# EASCapeRev1A.net
KiCad netlist of a schematic drawn in EAGLE
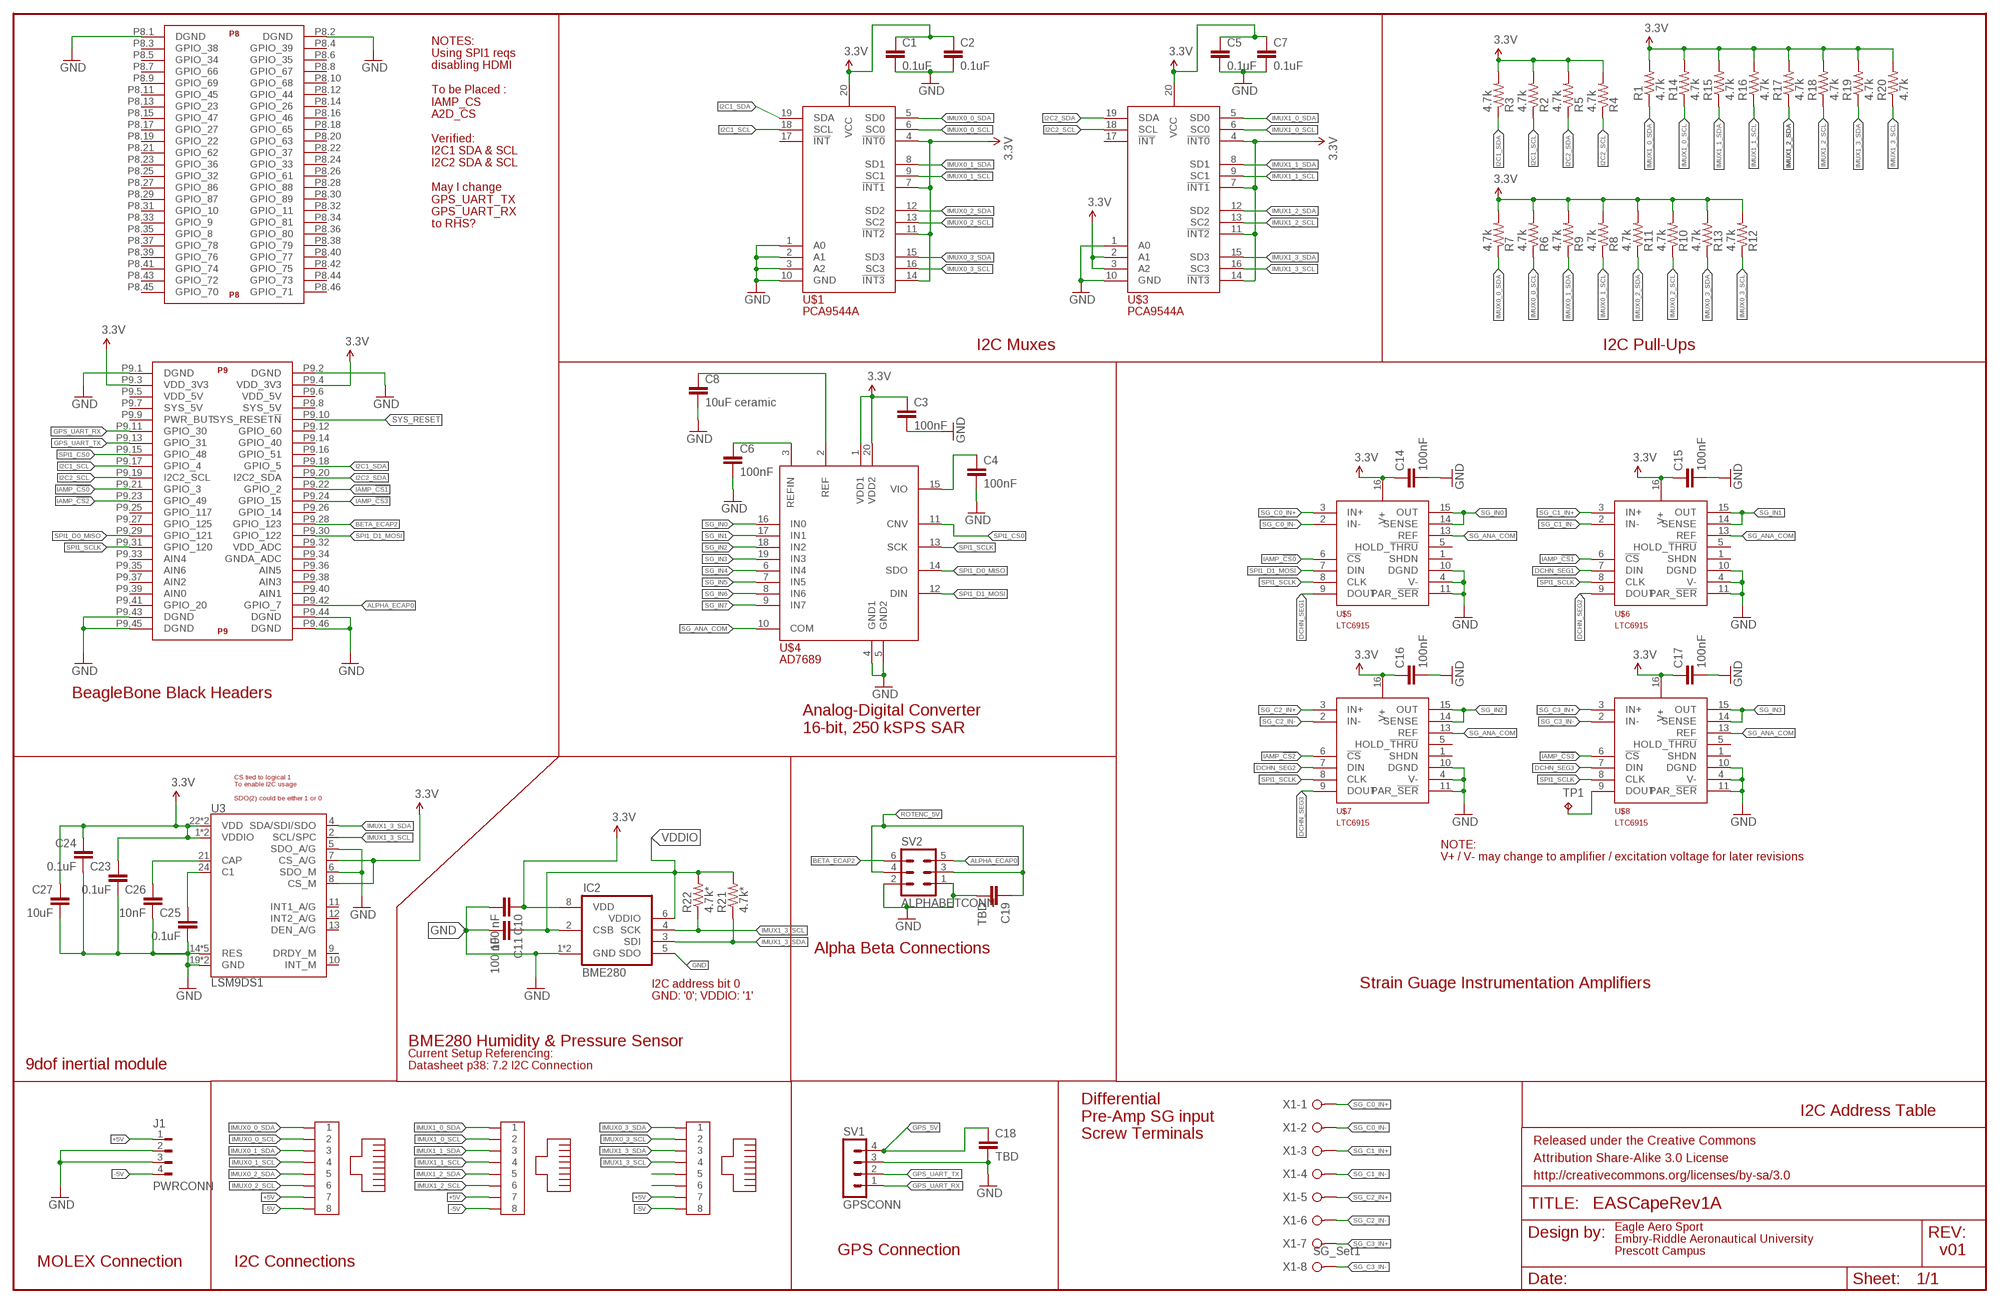
[diagram p0: schematic, sheet 1]

(export (version "E")
  (design (tool "Eeschema 10.0.6"))
  (components
    (comp (ref "C1")
      (value "0.1uF")
      (footprint "eagle-import:0805")
      (libsource (lib "eagle-import") (part "CAP0805"))
    )
    (comp (ref "C2")
      (value "0.1uF")
      (footprint "eagle-import:0805")
      (libsource (lib "eagle-import") (part "CAP0805"))
    )
    (comp (ref "C3")
      (value "100nF")
      (footprint "eagle-import:0805")
      (libsource (lib "eagle-import") (part "CAP0805"))
    )
    (comp (ref "C4")
      (value "100nF")
      (footprint "eagle-import:0805")
      (libsource (lib "eagle-import") (part "CAP0805"))
    )
    (comp (ref "C5")
      (value "0.1uF")
      (footprint "eagle-import:0805")
      (libsource (lib "eagle-import") (part "CAP0805"))
    )
    (comp (ref "C6")
      (value "100nF")
      (footprint "eagle-import:0805")
      (libsource (lib "eagle-import") (part "CAP0805"))
    )
    (comp (ref "C7")
      (value "0.1uF")
      (footprint "eagle-import:0805")
      (libsource (lib "eagle-import") (part "CAP0805"))
    )
    (comp (ref "C8")
      (value "10uF ceramic")
      (footprint "eagle-import:0805")
      (libsource (lib "eagle-import") (part "CAP0805"))
    )
    (comp (ref "C10")
      (value "100 nF")
      (footprint "eagle-import:0805")
      (libsource (lib "eagle-import") (part "CAP0805"))
    )
    (comp (ref "C11")
      (value "100 nF")
      (footprint "eagle-import:0805")
      (libsource (lib "eagle-import") (part "CAP0805"))
    )
    (comp (ref "C14")
      (value "100nF")
      (footprint "eagle-import:0805")
      (libsource (lib "eagle-import") (part "CAP0805"))
    )
    (comp (ref "C15")
      (value "100nF")
      (footprint "eagle-import:0805")
      (libsource (lib "eagle-import") (part "CAP0805"))
    )
    (comp (ref "C16")
      (value "100nF")
      (footprint "eagle-import:0805")
      (libsource (lib "eagle-import") (part "CAP0805"))
    )
    (comp (ref "C17")
      (value "100nF")
      (footprint "eagle-import:0805")
      (libsource (lib "eagle-import") (part "CAP0805"))
    )
    (comp (ref "C18")
      (value "TBD")
      (footprint "eagle-import:0805")
      (libsource (lib "eagle-import") (part "CAP0805"))
    )
    (comp (ref "C19")
      (value "TBD")
      (footprint "eagle-import:0805")
      (libsource (lib "eagle-import") (part "CAP0805"))
    )
    (comp (ref "C23")
      (value "0.1uF")
      (footprint "eagle-import:0805")
      (libsource (lib "eagle-import") (part "CAP0805"))
    )
    (comp (ref "C24")
      (value "0.1uF")
      (footprint "eagle-import:0805")
      (libsource (lib "eagle-import") (part "CAP0805"))
    )
    (comp (ref "C25")
      (value "0.1uF")
      (footprint "eagle-import:0805")
      (libsource (lib "eagle-import") (part "CAP0805"))
    )
    (comp (ref "C26")
      (value "10nF")
      (footprint "eagle-import:0805")
      (libsource (lib "eagle-import") (part "CAP0805"))
    )
    (comp (ref "C27")
      (value "10uF")
      (footprint "eagle-import:0805")
      (libsource (lib "eagle-import") (part "CAP0805"))
    )
    (comp (ref "FRAME1")
      (value "FRAME-LEDGER")
      (footprint "eagle-import:CREATIVE_COMMONS")
      (libsource (lib "eagle-import") (part "FRAME-LEDGER"))
    )
    (comp (ref "IC2")
      (value "BME280")
      (footprint "eagle-import:BME280")
      (libsource (lib "eagle-import") (part "BME280"))
    )
    (comp (ref "J1")
      (value "PWRCONN")
      (footprint "eagle-import:350211")
      (libsource (lib "eagle-import") (part "FLOPPY-4350211"))
    )
    (comp (ref "R1")
      (value "4.7k")
      (footprint "eagle-import:0805")
      (libsource (lib "eagle-import") (part "RESISTOR0805-RES"))
    )
    (comp (ref "R2")
      (value "4.7k")
      (footprint "eagle-import:0805")
      (libsource (lib "eagle-import") (part "RESISTOR0805-RES"))
    )
    (comp (ref "R3")
      (value "4.7k")
      (footprint "eagle-import:0805")
      (libsource (lib "eagle-import") (part "RESISTOR0805-RES"))
    )
    (comp (ref "R4")
      (value "4.7k")
      (footprint "eagle-import:0805")
      (libsource (lib "eagle-import") (part "RESISTOR0805-RES"))
    )
    (comp (ref "R5")
      (value "4.7k")
      (footprint "eagle-import:0805")
      (libsource (lib "eagle-import") (part "RESISTOR0805-RES"))
    )
    (comp (ref "R6")
      (value "4.7k")
      (footprint "eagle-import:0805")
      (libsource (lib "eagle-import") (part "RESISTOR0805-RES"))
    )
    (comp (ref "R7")
      (value "4.7k")
      (footprint "eagle-import:0805")
      (libsource (lib "eagle-import") (part "RESISTOR0805-RES"))
    )
    (comp (ref "R8")
      (value "4.7k")
      (footprint "eagle-import:0805")
      (libsource (lib "eagle-import") (part "RESISTOR0805-RES"))
    )
    (comp (ref "R9")
      (value "4.7k")
      (footprint "eagle-import:0805")
      (libsource (lib "eagle-import") (part "RESISTOR0805-RES"))
    )
    (comp (ref "R10")
      (value "4.7k")
      (footprint "eagle-import:0805")
      (libsource (lib "eagle-import") (part "RESISTOR0805-RES"))
    )
    (comp (ref "R11")
      (value "4.7k")
      (footprint "eagle-import:0805")
      (libsource (lib "eagle-import") (part "RESISTOR0805-RES"))
    )
    (comp (ref "R12")
      (value "4.7k")
      (footprint "eagle-import:0805")
      (libsource (lib "eagle-import") (part "RESISTOR0805-RES"))
    )
    (comp (ref "R13")
      (value "4.7k")
      (footprint "eagle-import:0805")
      (libsource (lib "eagle-import") (part "RESISTOR0805-RES"))
    )
    (comp (ref "R14")
      (value "4.7k")
      (footprint "eagle-import:0805")
      (libsource (lib "eagle-import") (part "RESISTOR0805-RES"))
    )
    (comp (ref "R15")
      (value "4.7k")
      (footprint "eagle-import:0805")
      (libsource (lib "eagle-import") (part "RESISTOR0805-RES"))
    )
    (comp (ref "R16")
      (value "4.7k")
      (footprint "eagle-import:0805")
      (libsource (lib "eagle-import") (part "RESISTOR0805-RES"))
    )
    (comp (ref "R17")
      (value "4.7k")
      (footprint "eagle-import:0805")
      (libsource (lib "eagle-import") (part "RESISTOR0805-RES"))
    )
    (comp (ref "R18")
      (value "4.7k")
      (footprint "eagle-import:0805")
      (libsource (lib "eagle-import") (part "RESISTOR0805-RES"))
    )
    (comp (ref "R19")
      (value "4.7k")
      (footprint "eagle-import:0805")
      (libsource (lib "eagle-import") (part "RESISTOR0805-RES"))
    )
    (comp (ref "R20")
      (value "4.7k")
      (footprint "eagle-import:0805")
      (libsource (lib "eagle-import") (part "RESISTOR0805-RES"))
    )
    (comp (ref "R21")
      (value "4.7k*")
      (footprint "eagle-import:0805")
      (libsource (lib "eagle-import") (part "RESISTOR0805-RES"))
    )
    (comp (ref "R22")
      (value "4.7k*")
      (footprint "eagle-import:0805")
      (libsource (lib "eagle-import") (part "RESISTOR0805-RES"))
    )
    (comp (ref "RJ1")
      (value "MOLEX-RJ45-SMT")
      (footprint "eagle-import:MOLEX-RJ45-SMT")
      (libsource (lib "eagle-import") (part "MOLEX-RJ45-SMT"))
    )
    (comp (ref "RJ2")
      (value "MOLEX-RJ45-SMT")
      (footprint "eagle-import:MOLEX-RJ45-SMT")
      (libsource (lib "eagle-import") (part "MOLEX-RJ45-SMT"))
    )
    (comp (ref "RJ3")
      (value "MOLEX-RJ45-SMT")
      (footprint "eagle-import:MOLEX-RJ45-SMT")
      (libsource (lib "eagle-import") (part "MOLEX-RJ45-SMT"))
    )
    (comp (ref "SV1")
      (value "GPSCONN")
      (footprint "eagle-import:MA04-1")
      (libsource (lib "eagle-import") (part "MA04-1"))
    )
    (comp (ref "SV2")
      (value "ALPHABETCONN")
      (footprint "eagle-import:MA03-2")
      (libsource (lib "eagle-import") (part "MA03-2"))
    )
    (comp (ref "TP1")
      (value "TPTP08R")
      (footprint "eagle-import:TP08R")
      (libsource (lib "eagle-import") (part "TPTP08R"))
    )
    (comp (ref "U$1")
      (value "PCA9544A")
      (footprint "eagle-import:TSSOP20")
      (libsource (lib "eagle-import") (part "PCA9544A"))
    )
    (comp (ref "U$2")
      (value "BEAGLE_BONE_BLACK_CAPE")
      (footprint "eagle-import:BEAGLE_BONE_BLACK_CAPE")
      (libsource (lib "eagle-import") (part "BEAGLE_BONE_BLACK_CAPE"))
    )
    (comp (ref "U$3")
      (value "PCA9544A")
      (footprint "eagle-import:TSSOP20")
      (libsource (lib "eagle-import") (part "PCA9544A"))
    )
    (comp (ref "U$4")
      (value "AD7689")
      (footprint "eagle-import:QFN20")
      (libsource (lib "eagle-import") (part "AD7689"))
    )
    (comp (ref "U$5")
      (value "LTC6915")
      (footprint "eagle-import:SSOP16")
      (libsource (lib "eagle-import") (part "LTC6915"))
    )
    (comp (ref "U$6")
      (value "LTC6915")
      (footprint "eagle-import:SSOP16")
      (libsource (lib "eagle-import") (part "LTC6915"))
    )
    (comp (ref "U$7")
      (value "LTC6915")
      (footprint "eagle-import:SSOP16")
      (libsource (lib "eagle-import") (part "LTC6915"))
    )
    (comp (ref "U$8")
      (value "LTC6915")
      (footprint "eagle-import:SSOP16")
      (libsource (lib "eagle-import") (part "LTC6915"))
    )
    (comp (ref "U3")
      (value "LSM9DS1")
      (footprint "eagle-import:LGA24-8X4")
      (libsource (lib "eagle-import") (part "LSM9DS1"))
    )
    (comp (ref "X1")
      (value "SG_Set1")
      (footprint "eagle-import:W237-8P")
      (libsource (lib "eagle-import") (part "W237-08P"))
    )
  )
  (nets
    (net (code "1") (name "+5V") (class "Default")
      (node (ref "J1") (pin "1") (pinfunction "1_1") (pintype "passive"))
      (node (ref "RJ1") (pin "7") (pinfunction "7_7") (pintype "bidirectional"))
      (node (ref "RJ2") (pin "7") (pinfunction "7_7") (pintype "bidirectional"))
      (node (ref "RJ3") (pin "7") (pinfunction "7_7") (pintype "bidirectional"))
    )
    (net (code "2") (name "-5V") (class "Default")
      (node (ref "J1") (pin "4") (pinfunction "4_4") (pintype "passive"))
      (node (ref "RJ1") (pin "8") (pinfunction "8_8") (pintype "bidirectional"))
      (node (ref "RJ2") (pin "8") (pinfunction "8_8") (pintype "bidirectional"))
      (node (ref "RJ3") (pin "8") (pinfunction "8_8") (pintype "bidirectional"))
    )
    (net (code "3") (name "/IAMP_~{CS0}") (class "Default")
      (node (ref "U$2") (pin "P9.21") (pinfunction "GPIO_3_P9.21") (pintype "bidirectional"))
      (node (ref "U$5") (pin "6") (pinfunction "~{CS}_6") (pintype "bidirectional"))
    )
    (net (code "4") (name "/IAMP_~{CS1}") (class "Default")
      (node (ref "U$2") (pin "P9.22") (pinfunction "GPIO_2_P9.22") (pintype "bidirectional"))
      (node (ref "U$6") (pin "6") (pinfunction "~{CS}_6") (pintype "bidirectional"))
    )
    (net (code "5") (name "/IAMP_~{CS2}") (class "Default")
      (node (ref "U$2") (pin "P9.23") (pinfunction "GPIO_49_P9.23") (pintype "bidirectional"))
      (node (ref "U$7") (pin "6") (pinfunction "~{CS}_6") (pintype "bidirectional"))
    )
    (net (code "6") (name "/IAMP_~{CS3}") (class "Default")
      (node (ref "U$2") (pin "P9.24") (pinfunction "GPIO_15_P9.24") (pintype "bidirectional"))
      (node (ref "U$8") (pin "6") (pinfunction "~{CS}_6") (pintype "bidirectional"))
    )
    (net (code "7") (name "3.3V") (class "Default")
      (node (ref "C1") (pin "1") (pinfunction "1_1") (pintype "passive"))
      (node (ref "C10") (pin "1") (pinfunction "1_1") (pintype "passive"))
      (node (ref "C14") (pin "1") (pinfunction "1_1") (pintype "passive"))
      (node (ref "C15") (pin "1") (pinfunction "1_1") (pintype "passive"))
      (node (ref "C16") (pin "1") (pinfunction "1_1") (pintype "passive"))
      (node (ref "C17") (pin "1") (pinfunction "1_1") (pintype "passive"))
      (node (ref "C2") (pin "1") (pinfunction "1_1") (pintype "passive"))
      (node (ref "C23") (pin "1") (pinfunction "1_1") (pintype "passive"))
      (node (ref "C24") (pin "1") (pinfunction "1_1") (pintype "passive"))
      (node (ref "C27") (pin "1") (pinfunction "1_1") (pintype "passive"))
      (node (ref "C3") (pin "1") (pinfunction "1_1") (pintype "passive"))
      (node (ref "C5") (pin "1") (pinfunction "1_1") (pintype "passive"))
      (node (ref "C7") (pin "1") (pinfunction "1_1") (pintype "passive"))
      (node (ref "IC2") (pin "8") (pinfunction "VDD_8") (pintype "power_in"))
      (node (ref "R1") (pin "2") (pinfunction "2_2") (pintype "passive"))
      (node (ref "R10") (pin "2") (pinfunction "2_2") (pintype "passive"))
      (node (ref "R11") (pin "2") (pinfunction "2_2") (pintype "passive"))
      (node (ref "R12") (pin "2") (pinfunction "2_2") (pintype "passive"))
      (node (ref "R13") (pin "2") (pinfunction "2_2") (pintype "passive"))
      (node (ref "R14") (pin "2") (pinfunction "2_2") (pintype "passive"))
      (node (ref "R15") (pin "2") (pinfunction "2_2") (pintype "passive"))
      (node (ref "R16") (pin "2") (pinfunction "2_2") (pintype "passive"))
      (node (ref "R17") (pin "2") (pinfunction "2_2") (pintype "passive"))
      (node (ref "R18") (pin "2") (pinfunction "2_2") (pintype "passive"))
      (node (ref "R19") (pin "2") (pinfunction "2_2") (pintype "passive"))
      (node (ref "R2") (pin "2") (pinfunction "2_2") (pintype "passive"))
      (node (ref "R20") (pin "2") (pinfunction "2_2") (pintype "passive"))
      (node (ref "R3") (pin "2") (pinfunction "2_2") (pintype "passive"))
      (node (ref "R4") (pin "2") (pinfunction "2_2") (pintype "passive"))
      (node (ref "R5") (pin "2") (pinfunction "2_2") (pintype "passive"))
      (node (ref "R6") (pin "2") (pinfunction "2_2") (pintype "passive"))
      (node (ref "R7") (pin "2") (pinfunction "2_2") (pintype "passive"))
      (node (ref "R8") (pin "2") (pinfunction "2_2") (pintype "passive"))
      (node (ref "R9") (pin "2") (pinfunction "2_2") (pintype "passive"))
      (node (ref "U$1") (pin "11") (pinfunction "~{INT2}_11") (pintype "input"))
      (node (ref "U$1") (pin "14") (pinfunction "~{INT3}_14") (pintype "input"))
      (node (ref "U$1") (pin "20") (pinfunction "VCC_20") (pintype "power_in"))
      (node (ref "U$1") (pin "4") (pinfunction "~{INT0}_4") (pintype "input"))
      (node (ref "U$1") (pin "7") (pinfunction "~{INT1}_7") (pintype "input"))
      (node (ref "U$2") (pin "P9.3") (pinfunction "VDD_3V3_P9.3") (pintype "bidirectional"))
      (node (ref "U$2") (pin "P9.4") (pinfunction "VDD_3V3_P9.4") (pintype "bidirectional"))
      (node (ref "U$3") (pin "11") (pinfunction "~{INT2}_11") (pintype "input"))
      (node (ref "U$3") (pin "14") (pinfunction "~{INT3}_14") (pintype "input"))
      (node (ref "U$3") (pin "2") (pinfunction "A1_2") (pintype "input"))
      (node (ref "U$3") (pin "20") (pinfunction "VCC_20") (pintype "power_in"))
      (node (ref "U$3") (pin "3") (pinfunction "A2_3") (pintype "input"))
      (node (ref "U$3") (pin "4") (pinfunction "~{INT0}_4") (pintype "input"))
      (node (ref "U$3") (pin "7") (pinfunction "~{INT1}_7") (pintype "input"))
      (node (ref "U$4") (pin "1") (pinfunction "VDD1_1") (pintype "bidirectional"))
      (node (ref "U$4") (pin "20") (pinfunction "VDD2_20") (pintype "bidirectional"))
      (node (ref "U$5") (pin "16") (pinfunction "V+_16") (pintype "bidirectional"))
      (node (ref "U$6") (pin "16") (pinfunction "V+_16") (pintype "bidirectional"))
      (node (ref "U$7") (pin "16") (pinfunction "V+_16") (pintype "bidirectional"))
      (node (ref "U$8") (pin "16") (pinfunction "V+_16") (pintype "bidirectional"))
      (node (ref "U3") (pin "1") (pinfunction "VDDIO_1") (pintype "bidirectional"))
      (node (ref "U3") (pin "22") (pinfunction "VDD_22") (pintype "bidirectional"))
      (node (ref "U3") (pin "23") (pinfunction "VDD_23") (pintype "bidirectional"))
      (node (ref "U3") (pin "3") (pinfunction "VDDIO_3") (pintype "bidirectional"))
      (node (ref "U3") (pin "7") (pinfunction "CS_A/G_7") (pintype "bidirectional"))
      (node (ref "U3") (pin "8") (pinfunction "CS_M_8") (pintype "bidirectional"))
    )
    (net (code "8") (name "ALPHA_ECAP0") (class "Default")
      (node (ref "SV2") (pin "5") (pinfunction "5_5") (pintype "passive"))
      (node (ref "U$2") (pin "P9.42") (pinfunction "GPIO_7_P9.42") (pintype "bidirectional"))
    )
    (net (code "9") (name "BETA_ECAP2") (class "Default")
      (node (ref "SV2") (pin "6") (pinfunction "6_6") (pintype "passive"))
      (node (ref "U$2") (pin "P9.28") (pinfunction "GPIO_123_P9.28") (pintype "bidirectional"))
    )
    (net (code "10") (name "DCHN_SEG1") (class "Default")
      (node (ref "U$5") (pin "9") (pinfunction "DOUT_9") (pintype "bidirectional"))
      (node (ref "U$6") (pin "7") (pinfunction "DIN_7") (pintype "bidirectional"))
    )
    (net (code "11") (name "DCHN_SEG2") (class "Default")
      (node (ref "U$6") (pin "9") (pinfunction "DOUT_9") (pintype "bidirectional"))
      (node (ref "U$7") (pin "7") (pinfunction "DIN_7") (pintype "bidirectional"))
    )
    (net (code "12") (name "DCHN_SEG3") (class "Default")
      (node (ref "U$7") (pin "9") (pinfunction "DOUT_9") (pintype "bidirectional"))
      (node (ref "U$8") (pin "7") (pinfunction "DIN_7") (pintype "bidirectional"))
    )
    (net (code "13") (name "GND") (class "Default")
      (node (ref "C1") (pin "2") (pinfunction "2_2") (pintype "passive"))
      (node (ref "C10") (pin "2") (pinfunction "2_2") (pintype "passive"))
      (node (ref "C11") (pin "2") (pinfunction "2_2") (pintype "passive"))
      (node (ref "C14") (pin "2") (pinfunction "2_2") (pintype "passive"))
      (node (ref "C15") (pin "2") (pinfunction "2_2") (pintype "passive"))
      (node (ref "C16") (pin "2") (pinfunction "2_2") (pintype "passive"))
      (node (ref "C17") (pin "2") (pinfunction "2_2") (pintype "passive"))
      (node (ref "C18") (pin "2") (pinfunction "2_2") (pintype "passive"))
      (node (ref "C19") (pin "2") (pinfunction "2_2") (pintype "passive"))
      (node (ref "C2") (pin "2") (pinfunction "2_2") (pintype "passive"))
      (node (ref "C23") (pin "2") (pinfunction "2_2") (pintype "passive"))
      (node (ref "C24") (pin "2") (pinfunction "2_2") (pintype "passive"))
      (node (ref "C25") (pin "2") (pinfunction "2_2") (pintype "passive"))
      (node (ref "C26") (pin "2") (pinfunction "2_2") (pintype "passive"))
      (node (ref "C27") (pin "2") (pinfunction "2_2") (pintype "passive"))
      (node (ref "C3") (pin "2") (pinfunction "2_2") (pintype "passive"))
      (node (ref "C4") (pin "2") (pinfunction "2_2") (pintype "passive"))
      (node (ref "C5") (pin "2") (pinfunction "2_2") (pintype "passive"))
      (node (ref "C6") (pin "2") (pinfunction "2_2") (pintype "passive"))
      (node (ref "C7") (pin "2") (pinfunction "2_2") (pintype "passive"))
      (node (ref "C8") (pin "2") (pinfunction "2_2") (pintype "passive"))
      (node (ref "IC2") (pin "1") (pinfunction "GND_1") (pintype "power_in"))
      (node (ref "IC2") (pin "5") (pinfunction "SDO_5") (pintype "input"))
      (node (ref "IC2") (pin "7") (pinfunction "GND_7") (pintype "power_in"))
      (node (ref "J1") (pin "2") (pinfunction "2_2") (pintype "passive"))
      (node (ref "J1") (pin "3") (pinfunction "3_3") (pintype "passive"))
      (node (ref "SV1") (pin "3") (pinfunction "3_3") (pintype "passive"))
      (node (ref "SV2") (pin "1") (pinfunction "1_1") (pintype "passive"))
      (node (ref "SV2") (pin "2") (pinfunction "2_2") (pintype "passive"))
      (node (ref "U$1") (pin "1") (pinfunction "A0_1") (pintype "input"))
      (node (ref "U$1") (pin "10") (pinfunction "GND_10") (pintype "power_in"))
      (node (ref "U$1") (pin "2") (pinfunction "A1_2") (pintype "input"))
      (node (ref "U$1") (pin "3") (pinfunction "A2_3") (pintype "input"))
      (node (ref "U$2") (pin "P8.1") (pinfunction "DGND_P8.1") (pintype "bidirectional"))
      (node (ref "U$2") (pin "P8.2") (pinfunction "DGND_P8.2") (pintype "bidirectional"))
      (node (ref "U$2") (pin "P9.1") (pinfunction "DGND_P9.1") (pintype "bidirectional"))
      (node (ref "U$2") (pin "P9.2") (pinfunction "DGND_P9.2") (pintype "bidirectional"))
      (node (ref "U$2") (pin "P9.43") (pinfunction "DGND_P9.43") (pintype "bidirectional"))
      (node (ref "U$2") (pin "P9.44") (pinfunction "DGND_P9.44") (pintype "bidirectional"))
      (node (ref "U$2") (pin "P9.45") (pinfunction "DGND_P9.45") (pintype "bidirectional"))
      (node (ref "U$2") (pin "P9.46") (pinfunction "DGND_P9.46") (pintype "bidirectional"))
      (node (ref "U$3") (pin "1") (pinfunction "A0_1") (pintype "input"))
      (node (ref "U$3") (pin "10") (pinfunction "GND_10") (pintype "power_in"))
      (node (ref "U$4") (pin "4") (pinfunction "GND1_4") (pintype "bidirectional"))
      (node (ref "U$4") (pin "5") (pinfunction "GND2_5") (pintype "bidirectional"))
      (node (ref "U$5") (pin "10") (pinfunction "DGND_10") (pintype "bidirectional"))
      (node (ref "U$5") (pin "11") (pinfunction "PAR_~{SER}_11") (pintype "bidirectional"))
      (node (ref "U$5") (pin "4") (pinfunction "V-_4") (pintype "bidirectional"))
      (node (ref "U$6") (pin "10") (pinfunction "DGND_10") (pintype "bidirectional"))
      (node (ref "U$6") (pin "11") (pinfunction "PAR_~{SER}_11") (pintype "bidirectional"))
      (node (ref "U$6") (pin "4") (pinfunction "V-_4") (pintype "bidirectional"))
      (node (ref "U$7") (pin "10") (pinfunction "DGND_10") (pintype "bidirectional"))
      (node (ref "U$7") (pin "11") (pinfunction "PAR_~{SER}_11") (pintype "bidirectional"))
      (node (ref "U$7") (pin "4") (pinfunction "V-_4") (pintype "bidirectional"))
      (node (ref "U$8") (pin "10") (pinfunction "DGND_10") (pintype "bidirectional"))
      (node (ref "U$8") (pin "11") (pinfunction "PAR_~{SER}_11") (pintype "bidirectional"))
      (node (ref "U$8") (pin "4") (pinfunction "V-_4") (pintype "bidirectional"))
      (node (ref "U3") (pin "14") (pinfunction "RES_14") (pintype "bidirectional"))
      (node (ref "U3") (pin "15") (pinfunction "RES_15") (pintype "bidirectional"))
      (node (ref "U3") (pin "16") (pinfunction "RES_16") (pintype "bidirectional"))
      (node (ref "U3") (pin "17") (pinfunction "RES_17") (pintype "bidirectional"))
      (node (ref "U3") (pin "18") (pinfunction "RES_18") (pintype "bidirectional"))
      (node (ref "U3") (pin "19") (pinfunction "GND_19") (pintype "bidirectional"))
      (node (ref "U3") (pin "20") (pinfunction "GND_20") (pintype "bidirectional"))
      (node (ref "U3") (pin "5") (pinfunction "SDO_A/G_5") (pintype "bidirectional"))
      (node (ref "U3") (pin "6") (pinfunction "SDO_M_6") (pintype "bidirectional"))
    )
    (net (code "14") (name "GPS_5V") (class "Default")
      (node (ref "C18") (pin "1") (pinfunction "1_1") (pintype "passive"))
      (node (ref "SV1") (pin "4") (pinfunction "4_4") (pintype "passive"))
    )
    (net (code "15") (name "GPS_UART_RX") (class "Default")
      (node (ref "SV1") (pin "1") (pinfunction "1_1") (pintype "passive"))
      (node (ref "U$2") (pin "P9.11") (pinfunction "GPIO_30_P9.11") (pintype "bidirectional"))
    )
    (net (code "16") (name "GPS_UART_TX") (class "Default")
      (node (ref "SV1") (pin "2") (pinfunction "2_2") (pintype "passive"))
      (node (ref "U$2") (pin "P9.13") (pinfunction "GPIO_31_P9.13") (pintype "bidirectional"))
    )
    (net (code "17") (name "I2C1_SCL") (class "Default")
      (node (ref "R2") (pin "1") (pinfunction "1_1") (pintype "passive"))
      (node (ref "U$1") (pin "18") (pinfunction "SCL_18") (pintype "input"))
      (node (ref "U$2") (pin "P9.17") (pinfunction "GPIO_4_P9.17") (pintype "bidirectional"))
    )
    (net (code "18") (name "I2C1_SDA") (class "Default")
      (node (ref "R3") (pin "1") (pinfunction "1_1") (pintype "passive"))
      (node (ref "U$1") (pin "19") (pinfunction "SDA_19") (pintype "bidirectional"))
      (node (ref "U$2") (pin "P9.18") (pinfunction "GPIO_5_P9.18") (pintype "bidirectional"))
    )
    (net (code "19") (name "I2C2_SCL") (class "Default")
      (node (ref "R4") (pin "1") (pinfunction "1_1") (pintype "passive"))
      (node (ref "U$2") (pin "P9.19") (pinfunction "I2C2_SCL_P9.19") (pintype "bidirectional"))
      (node (ref "U$3") (pin "18") (pinfunction "SCL_18") (pintype "input"))
    )
    (net (code "20") (name "I2C2_SDA") (class "Default")
      (node (ref "R5") (pin "1") (pinfunction "1_1") (pintype "passive"))
      (node (ref "U$2") (pin "P9.20") (pinfunction "I2C2_SDA_P9.20") (pintype "bidirectional"))
      (node (ref "U$3") (pin "19") (pinfunction "SDA_19") (pintype "bidirectional"))
    )
    (net (code "21") (name "IMUX0_0_SCL") (class "Default")
      (node (ref "R6") (pin "1") (pinfunction "1_1") (pintype "passive"))
      (node (ref "RJ1") (pin "2") (pinfunction "2_2") (pintype "bidirectional"))
      (node (ref "U$1") (pin "6") (pinfunction "SC0_6") (pintype "output"))
    )
    (net (code "22") (name "IMUX0_0_SDA") (class "Default")
      (node (ref "R7") (pin "1") (pinfunction "1_1") (pintype "passive"))
      (node (ref "RJ1") (pin "1") (pinfunction "1_1") (pintype "bidirectional"))
      (node (ref "U$1") (pin "5") (pinfunction "SD0_5") (pintype "bidirectional"))
    )
    (net (code "23") (name "IMUX0_1_SCL") (class "Default")
      (node (ref "R8") (pin "1") (pinfunction "1_1") (pintype "passive"))
      (node (ref "RJ1") (pin "4") (pinfunction "4_4") (pintype "bidirectional"))
      (node (ref "U$1") (pin "9") (pinfunction "SC1_9") (pintype "output"))
    )
    (net (code "24") (name "IMUX0_1_SDA") (class "Default")
      (node (ref "R9") (pin "1") (pinfunction "1_1") (pintype "passive"))
      (node (ref "RJ1") (pin "3") (pinfunction "3_3") (pintype "bidirectional"))
      (node (ref "U$1") (pin "8") (pinfunction "SD1_8") (pintype "bidirectional"))
    )
    (net (code "25") (name "IMUX0_2_SCL") (class "Default")
      (node (ref "R10") (pin "1") (pinfunction "1_1") (pintype "passive"))
      (node (ref "RJ1") (pin "6") (pinfunction "6_6") (pintype "bidirectional"))
      (node (ref "U$1") (pin "13") (pinfunction "SC2_13") (pintype "output"))
    )
    (net (code "26") (name "IMUX0_2_SDA") (class "Default")
      (node (ref "R11") (pin "1") (pinfunction "1_1") (pintype "passive"))
      (node (ref "RJ1") (pin "5") (pinfunction "5_5") (pintype "bidirectional"))
      (node (ref "U$1") (pin "12") (pinfunction "SD2_12") (pintype "bidirectional"))
    )
    (net (code "27") (name "IMUX0_3_SCL") (class "Default")
      (node (ref "R12") (pin "1") (pinfunction "1_1") (pintype "passive"))
      (node (ref "RJ3") (pin "2") (pinfunction "2_2") (pintype "bidirectional"))
      (node (ref "U$1") (pin "16") (pinfunction "SC3_16") (pintype "output"))
    )
    (net (code "28") (name "IMUX0_3_SDA") (class "Default")
      (node (ref "R13") (pin "1") (pinfunction "1_1") (pintype "passive"))
      (node (ref "RJ3") (pin "1") (pinfunction "1_1") (pintype "bidirectional"))
      (node (ref "U$1") (pin "15") (pinfunction "SD3_15") (pintype "bidirectional"))
    )
    (net (code "29") (name "IMUX1_0_SCL") (class "Default")
      (node (ref "R14") (pin "1") (pinfunction "1_1") (pintype "passive"))
      (node (ref "RJ2") (pin "2") (pinfunction "2_2") (pintype "bidirectional"))
      (node (ref "U$3") (pin "6") (pinfunction "SC0_6") (pintype "output"))
    )
    (net (code "30") (name "IMUX1_0_SDA") (class "Default")
      (node (ref "R1") (pin "1") (pinfunction "1_1") (pintype "passive"))
      (node (ref "RJ2") (pin "1") (pinfunction "1_1") (pintype "bidirectional"))
      (node (ref "U$3") (pin "5") (pinfunction "SD0_5") (pintype "bidirectional"))
    )
    (net (code "31") (name "IMUX1_1_SCL") (class "Default")
      (node (ref "R16") (pin "1") (pinfunction "1_1") (pintype "passive"))
      (node (ref "RJ2") (pin "4") (pinfunction "4_4") (pintype "bidirectional"))
      (node (ref "U$3") (pin "9") (pinfunction "SC1_9") (pintype "output"))
    )
    (net (code "32") (name "IMUX1_1_SDA") (class "Default")
      (node (ref "R15") (pin "1") (pinfunction "1_1") (pintype "passive"))
      (node (ref "RJ2") (pin "3") (pinfunction "3_3") (pintype "bidirectional"))
      (node (ref "U$3") (pin "8") (pinfunction "SD1_8") (pintype "bidirectional"))
    )
    (net (code "33") (name "IMUX1_2_SCL") (class "Default")
      (node (ref "R18") (pin "1") (pinfunction "1_1") (pintype "passive"))
      (node (ref "RJ2") (pin "6") (pinfunction "6_6") (pintype "bidirectional"))
      (node (ref "U$3") (pin "13") (pinfunction "SC2_13") (pintype "output"))
    )
    (net (code "34") (name "IMUX1_2_SDA") (class "Default")
      (node (ref "R17") (pin "1") (pinfunction "1_1") (pintype "passive"))
      (node (ref "RJ2") (pin "5") (pinfunction "5_5") (pintype "bidirectional"))
      (node (ref "U$3") (pin "12") (pinfunction "SD2_12") (pintype "bidirectional"))
    )
    (net (code "35") (name "IMUX1_3_SCL") (class "Default")
      (node (ref "IC2") (pin "4") (pinfunction "SCK_4") (pintype "bidirectional"))
      (node (ref "R20") (pin "1") (pinfunction "1_1") (pintype "passive"))
      (node (ref "R22") (pin "1") (pinfunction "1_1") (pintype "passive"))
      (node (ref "RJ3") (pin "4") (pinfunction "4_4") (pintype "bidirectional"))
      (node (ref "U$3") (pin "16") (pinfunction "SC3_16") (pintype "output"))
      (node (ref "U3") (pin "2") (pinfunction "SCL/SPC_2") (pintype "bidirectional"))
    )
    (net (code "36") (name "IMUX1_3_SDA") (class "Default")
      (node (ref "IC2") (pin "3") (pinfunction "SDI_3") (pintype "bidirectional"))
      (node (ref "R19") (pin "1") (pinfunction "1_1") (pintype "passive"))
      (node (ref "R21") (pin "1") (pinfunction "1_1") (pintype "passive"))
      (node (ref "RJ3") (pin "3") (pinfunction "3_3") (pintype "bidirectional"))
      (node (ref "U$3") (pin "15") (pinfunction "SD3_15") (pintype "bidirectional"))
      (node (ref "U3") (pin "4") (pinfunction "SDA/SDI/SDO_4") (pintype "bidirectional"))
    )
    (net (code "37") (name "Net-(U$4-REF)") (class "Default")
      (node (ref "C8") (pin "1") (pinfunction "1_1") (pintype "passive"))
      (node (ref "U$4") (pin "2") (pinfunction "REF_2") (pintype "bidirectional"))
    )
    (net (code "38") (name "Net-(U$4-REFIN)") (class "Default")
      (node (ref "C6") (pin "1") (pinfunction "1_1") (pintype "passive"))
      (node (ref "U$4") (pin "3") (pinfunction "REFIN_3") (pintype "bidirectional"))
    )
    (net (code "39") (name "Net-(U$4-VIO)") (class "Default")
      (node (ref "C4") (pin "1") (pinfunction "1_1") (pintype "passive"))
      (node (ref "U$4") (pin "15") (pinfunction "VIO_15") (pintype "bidirectional"))
    )
    (net (code "40") (name "Net-(U$8-DOUT)") (class "Default")
      (node (ref "TP1") (pin "TP") (pinfunction "TP_TP") (pintype "input"))
      (node (ref "U$8") (pin "9") (pinfunction "DOUT_9") (pintype "bidirectional"))
    )
    (net (code "41") (name "Net-(U3-C1)") (class "Default")
      (node (ref "C25") (pin "1") (pinfunction "1_1") (pintype "passive"))
      (node (ref "U3") (pin "24") (pinfunction "C1_24") (pintype "bidirectional"))
    )
    (net (code "42") (name "Net-(U3-CAP)") (class "Default")
      (node (ref "C26") (pin "1") (pinfunction "1_1") (pintype "passive"))
      (node (ref "U3") (pin "21") (pinfunction "CAP_21") (pintype "bidirectional"))
    )
    (net (code "43") (name "ROTENC_5V") (class "Default")
      (node (ref "C19") (pin "1") (pinfunction "1_1") (pintype "passive"))
      (node (ref "SV2") (pin "3") (pinfunction "3_3") (pintype "passive"))
      (node (ref "SV2") (pin "4") (pinfunction "4_4") (pintype "passive"))
    )
    (net (code "44") (name "SG_ANA_COM") (class "Default")
      (node (ref "U$4") (pin "10") (pinfunction "COM_10") (pintype "bidirectional"))
      (node (ref "U$5") (pin "13") (pinfunction "REF_13") (pintype "bidirectional"))
      (node (ref "U$6") (pin "13") (pinfunction "REF_13") (pintype "bidirectional"))
      (node (ref "U$7") (pin "13") (pinfunction "REF_13") (pintype "bidirectional"))
      (node (ref "U$8") (pin "13") (pinfunction "REF_13") (pintype "bidirectional"))
    )
    (net (code "45") (name "SG_C0_IN+") (class "Default")
      (node (ref "U$5") (pin "3") (pinfunction "IN+_3") (pintype "bidirectional"))
      (node (ref "X1") (pin "1") (pinfunction "KL_1") (pintype "passive"))
    )
    (net (code "46") (name "SG_C0_IN-") (class "Default")
      (node (ref "U$5") (pin "2") (pinfunction "IN-_2") (pintype "bidirectional"))
      (node (ref "X1") (pin "2") (pinfunction "KL_2") (pintype "passive"))
    )
    (net (code "47") (name "SG_C1_IN+") (class "Default")
      (node (ref "U$6") (pin "3") (pinfunction "IN+_3") (pintype "bidirectional"))
      (node (ref "X1") (pin "3") (pinfunction "KL_3") (pintype "passive"))
    )
    (net (code "48") (name "SG_C1_IN-") (class "Default")
      (node (ref "U$6") (pin "2") (pinfunction "IN-_2") (pintype "bidirectional"))
      (node (ref "X1") (pin "4") (pinfunction "KL_4") (pintype "passive"))
    )
    (net (code "49") (name "SG_C2_IN+") (class "Default")
      (node (ref "U$7") (pin "3") (pinfunction "IN+_3") (pintype "bidirectional"))
      (node (ref "X1") (pin "5") (pinfunction "KL_5") (pintype "passive"))
    )
    (net (code "50") (name "SG_C2_IN-") (class "Default")
      (node (ref "U$7") (pin "2") (pinfunction "IN-_2") (pintype "bidirectional"))
      (node (ref "X1") (pin "6") (pinfunction "KL_6") (pintype "passive"))
    )
    (net (code "51") (name "SG_C3_IN+") (class "Default")
      (node (ref "U$8") (pin "3") (pinfunction "IN+_3") (pintype "bidirectional"))
      (node (ref "X1") (pin "7") (pinfunction "KL_7") (pintype "passive"))
    )
    (net (code "52") (name "SG_C3_IN-") (class "Default")
      (node (ref "U$8") (pin "2") (pinfunction "IN-_2") (pintype "bidirectional"))
      (node (ref "X1") (pin "8") (pinfunction "KL_8") (pintype "passive"))
    )
    (net (code "53") (name "SG_IN0") (class "Default")
      (node (ref "U$4") (pin "16") (pinfunction "IN0_16") (pintype "bidirectional"))
      (node (ref "U$5") (pin "14") (pinfunction "SENSE_14") (pintype "bidirectional"))
      (node (ref "U$5") (pin "15") (pinfunction "OUT_15") (pintype "bidirectional"))
    )
    (net (code "54") (name "SG_IN1") (class "Default")
      (node (ref "U$4") (pin "17") (pinfunction "IN1_17") (pintype "bidirectional"))
      (node (ref "U$6") (pin "14") (pinfunction "SENSE_14") (pintype "bidirectional"))
      (node (ref "U$6") (pin "15") (pinfunction "OUT_15") (pintype "bidirectional"))
    )
    (net (code "55") (name "SG_IN2") (class "Default")
      (node (ref "U$4") (pin "18") (pinfunction "IN2_18") (pintype "bidirectional"))
      (node (ref "U$7") (pin "14") (pinfunction "SENSE_14") (pintype "bidirectional"))
      (node (ref "U$7") (pin "15") (pinfunction "OUT_15") (pintype "bidirectional"))
    )
    (net (code "56") (name "SG_IN3") (class "Default")
      (node (ref "U$4") (pin "19") (pinfunction "IN3_19") (pintype "bidirectional"))
      (node (ref "U$8") (pin "14") (pinfunction "SENSE_14") (pintype "bidirectional"))
      (node (ref "U$8") (pin "15") (pinfunction "OUT_15") (pintype "bidirectional"))
    )
    (net (code "57") (name "SG_IN4") (class "Default")
      (node (ref "U$4") (pin "6") (pinfunction "IN4_6") (pintype "bidirectional"))
    )
    (net (code "58") (name "SG_IN5") (class "Default")
      (node (ref "U$4") (pin "7") (pinfunction "IN5_7") (pintype "bidirectional"))
    )
    (net (code "59") (name "SG_IN6") (class "Default")
      (node (ref "U$4") (pin "8") (pinfunction "IN6_8") (pintype "bidirectional"))
    )
    (net (code "60") (name "SG_IN7") (class "Default")
      (node (ref "U$4") (pin "9") (pinfunction "IN7_9") (pintype "bidirectional"))
    )
    (net (code "61") (name "SPI1_CS0") (class "Default")
      (node (ref "U$2") (pin "P9.15") (pinfunction "GPIO_48_P9.15") (pintype "bidirectional"))
      (node (ref "U$4") (pin "11") (pinfunction "CNV_11") (pintype "bidirectional"))
    )
    (net (code "62") (name "SPI1_D0_MISO") (class "Default")
      (node (ref "U$2") (pin "P9.29") (pinfunction "GPIO_121_P9.29") (pintype "bidirectional"))
      (node (ref "U$4") (pin "14") (pinfunction "SDO_14") (pintype "bidirectional"))
    )
    (net (code "63") (name "SPI1_D1_MOSI") (class "Default")
      (node (ref "U$2") (pin "P9.30") (pinfunction "GPIO_122_P9.30") (pintype "bidirectional"))
      (node (ref "U$4") (pin "12") (pinfunction "DIN_12") (pintype "bidirectional"))
      (node (ref "U$5") (pin "7") (pinfunction "DIN_7") (pintype "bidirectional"))
    )
    (net (code "64") (name "SPI1_SCLK") (class "Default")
      (node (ref "U$2") (pin "P9.31") (pinfunction "GPIO_120_P9.31") (pintype "bidirectional"))
      (node (ref "U$4") (pin "13") (pinfunction "SCK_13") (pintype "bidirectional"))
      (node (ref "U$5") (pin "8") (pinfunction "CLK_8") (pintype "bidirectional"))
      (node (ref "U$6") (pin "8") (pinfunction "CLK_8") (pintype "bidirectional"))
      (node (ref "U$7") (pin "8") (pinfunction "CLK_8") (pintype "bidirectional"))
      (node (ref "U$8") (pin "8") (pinfunction "CLK_8") (pintype "bidirectional"))
    )
    (net (code "65") (name "SYS_RESET") (class "Default")
      (node (ref "U$2") (pin "P9.10") (pinfunction "SYS_RESET~{N}_P9.10") (pintype "bidirectional"))
    )
    (net (code "66") (name "VDDIO") (class "Default")
      (node (ref "C11") (pin "1") (pinfunction "1_1") (pintype "passive"))
      (node (ref "IC2") (pin "2") (pinfunction "CSB_2") (pintype "input"))
      (node (ref "IC2") (pin "6") (pinfunction "VDDIO_6") (pintype "power_in"))
      (node (ref "R21") (pin "2") (pinfunction "2_2") (pintype "passive"))
      (node (ref "R22") (pin "2") (pinfunction "2_2") (pintype "passive"))
    )
    (net (code "67") (name "unconnected-(RJ3-Pad5)") (class "Default")
      (node (ref "RJ3") (pin "5") (pinfunction "5_5") (pintype "bidirectional"))
    )
    (net (code "68") (name "unconnected-(RJ3-Pad6)") (class "Default")
      (node (ref "RJ3") (pin "6") (pinfunction "6_6") (pintype "bidirectional"))
    )
    (net (code "69") (name "unconnected-(U$1-~{INT}-Pad17)") (class "Default")
      (node (ref "U$1") (pin "17") (pinfunction "~{INT}_17") (pintype "output"))
    )
    (net (code "70") (name "unconnected-(U$2A-GPIO_8-PadP8.35)") (class "Default")
      (node (ref "U$2") (pin "P8.35") (pinfunction "GPIO_8_P8.35") (pintype "bidirectional"))
    )
    (net (code "71") (name "unconnected-(U$2A-GPIO_9-PadP8.33)") (class "Default")
      (node (ref "U$2") (pin "P8.33") (pinfunction "GPIO_9_P8.33") (pintype "bidirectional"))
    )
    (net (code "72") (name "unconnected-(U$2A-GPIO_10-PadP8.31)") (class "Default")
      (node (ref "U$2") (pin "P8.31") (pinfunction "GPIO_10_P8.31") (pintype "bidirectional"))
    )
    (net (code "73") (name "unconnected-(U$2A-GPIO_11-PadP8.32)") (class "Default")
      (node (ref "U$2") (pin "P8.32") (pinfunction "GPIO_11_P8.32") (pintype "bidirectional"))
    )
    (net (code "74") (name "unconnected-(U$2A-GPIO_22-PadP8.19)") (class "Default")
      (node (ref "U$2") (pin "P8.19") (pinfunction "GPIO_22_P8.19") (pintype "bidirectional"))
    )
    (net (code "75") (name "unconnected-(U$2A-GPIO_23-PadP8.13)") (class "Default")
      (node (ref "U$2") (pin "P8.13") (pinfunction "GPIO_23_P8.13") (pintype "bidirectional"))
    )
    (net (code "76") (name "unconnected-(U$2A-GPIO_26-PadP8.14)") (class "Default")
      (node (ref "U$2") (pin "P8.14") (pinfunction "GPIO_26_P8.14") (pintype "bidirectional"))
    )
    (net (code "77") (name "unconnected-(U$2A-GPIO_27-PadP8.17)") (class "Default")
      (node (ref "U$2") (pin "P8.17") (pinfunction "GPIO_27_P8.17") (pintype "bidirectional"))
    )
    (net (code "78") (name "unconnected-(U$2A-GPIO_32-PadP8.25)") (class "Default")
      (node (ref "U$2") (pin "P8.25") (pinfunction "GPIO_32_P8.25") (pintype "bidirectional"))
    )
    (net (code "79") (name "unconnected-(U$2A-GPIO_33-PadP8.24)") (class "Default")
      (node (ref "U$2") (pin "P8.24") (pinfunction "GPIO_33_P8.24") (pintype "bidirectional"))
    )
    (net (code "80") (name "unconnected-(U$2A-GPIO_34-PadP8.5)") (class "Default")
      (node (ref "U$2") (pin "P8.5") (pinfunction "GPIO_34_P8.5") (pintype "bidirectional"))
    )
    (net (code "81") (name "unconnected-(U$2A-GPIO_35-PadP8.6)") (class "Default")
      (node (ref "U$2") (pin "P8.6") (pinfunction "GPIO_35_P8.6") (pintype "bidirectional"))
    )
    (net (code "82") (name "unconnected-(U$2A-GPIO_36-PadP8.23)") (class "Default")
      (node (ref "U$2") (pin "P8.23") (pinfunction "GPIO_36_P8.23") (pintype "bidirectional"))
    )
    (net (code "83") (name "unconnected-(U$2A-GPIO_37-PadP8.22)") (class "Default")
      (node (ref "U$2") (pin "P8.22") (pinfunction "GPIO_37_P8.22") (pintype "bidirectional"))
    )
    (net (code "84") (name "unconnected-(U$2A-GPIO_38-PadP8.3)") (class "Default")
      (node (ref "U$2") (pin "P8.3") (pinfunction "GPIO_38_P8.3") (pintype "bidirectional"))
    )
    (net (code "85") (name "unconnected-(U$2A-GPIO_39-PadP8.4)") (class "Default")
      (node (ref "U$2") (pin "P8.4") (pinfunction "GPIO_39_P8.4") (pintype "bidirectional"))
    )
    (net (code "86") (name "unconnected-(U$2A-GPIO_44-PadP8.12)") (class "Default")
      (node (ref "U$2") (pin "P8.12") (pinfunction "GPIO_44_P8.12") (pintype "bidirectional"))
    )
    (net (code "87") (name "unconnected-(U$2A-GPIO_45-PadP8.11)") (class "Default")
      (node (ref "U$2") (pin "P8.11") (pinfunction "GPIO_45_P8.11") (pintype "bidirectional"))
    )
    (net (code "88") (name "unconnected-(U$2A-GPIO_46-PadP8.16)") (class "Default")
      (node (ref "U$2") (pin "P8.16") (pinfunction "GPIO_46_P8.16") (pintype "bidirectional"))
    )
    (net (code "89") (name "unconnected-(U$2A-GPIO_47-PadP8.15)") (class "Default")
      (node (ref "U$2") (pin "P8.15") (pinfunction "GPIO_47_P8.15") (pintype "bidirectional"))
    )
    (net (code "90") (name "unconnected-(U$2A-GPIO_61-PadP8.26)") (class "Default")
      (node (ref "U$2") (pin "P8.26") (pinfunction "GPIO_61_P8.26") (pintype "bidirectional"))
    )
    (net (code "91") (name "unconnected-(U$2A-GPIO_62-PadP8.21)") (class "Default")
      (node (ref "U$2") (pin "P8.21") (pinfunction "GPIO_62_P8.21") (pintype "bidirectional"))
    )
    (net (code "92") (name "unconnected-(U$2A-GPIO_63-PadP8.20)") (class "Default")
      (node (ref "U$2") (pin "P8.20") (pinfunction "GPIO_63_P8.20") (pintype "bidirectional"))
    )
    (net (code "93") (name "unconnected-(U$2A-GPIO_65-PadP8.18)") (class "Default")
      (node (ref "U$2") (pin "P8.18") (pinfunction "GPIO_65_P8.18") (pintype "bidirectional"))
    )
    (net (code "94") (name "unconnected-(U$2A-GPIO_66-PadP8.7)") (class "Default")
      (node (ref "U$2") (pin "P8.7") (pinfunction "GPIO_66_P8.7") (pintype "bidirectional"))
    )
    (net (code "95") (name "unconnected-(U$2A-GPIO_67-PadP8.8)") (class "Default")
      (node (ref "U$2") (pin "P8.8") (pinfunction "GPIO_67_P8.8") (pintype "bidirectional"))
    )
    (net (code "96") (name "unconnected-(U$2A-GPIO_68-PadP8.10)") (class "Default")
      (node (ref "U$2") (pin "P8.10") (pinfunction "GPIO_68_P8.10") (pintype "bidirectional"))
    )
    (net (code "97") (name "unconnected-(U$2A-GPIO_69-PadP8.9)") (class "Default")
      (node (ref "U$2") (pin "P8.9") (pinfunction "GPIO_69_P8.9") (pintype "bidirectional"))
    )
    (net (code "98") (name "unconnected-(U$2A-GPIO_70-PadP8.45)") (class "Default")
      (node (ref "U$2") (pin "P8.45") (pinfunction "GPIO_70_P8.45") (pintype "bidirectional"))
    )
    (net (code "99") (name "unconnected-(U$2A-GPIO_71-PadP8.46)") (class "Default")
      (node (ref "U$2") (pin "P8.46") (pinfunction "GPIO_71_P8.46") (pintype "bidirectional"))
    )
    (net (code "100") (name "unconnected-(U$2A-GPIO_72-PadP8.43)") (class "Default")
      (node (ref "U$2") (pin "P8.43") (pinfunction "GPIO_72_P8.43") (pintype "bidirectional"))
    )
    (net (code "101") (name "unconnected-(U$2A-GPIO_73-PadP8.44)") (class "Default")
      (node (ref "U$2") (pin "P8.44") (pinfunction "GPIO_73_P8.44") (pintype "bidirectional"))
    )
    (net (code "102") (name "unconnected-(U$2A-GPIO_74-PadP8.41)") (class "Default")
      (node (ref "U$2") (pin "P8.41") (pinfunction "GPIO_74_P8.41") (pintype "bidirectional"))
    )
    (net (code "103") (name "unconnected-(U$2A-GPIO_75-PadP8.42)") (class "Default")
      (node (ref "U$2") (pin "P8.42") (pinfunction "GPIO_75_P8.42") (pintype "bidirectional"))
    )
    (net (code "104") (name "unconnected-(U$2A-GPIO_76-PadP8.39)") (class "Default")
      (node (ref "U$2") (pin "P8.39") (pinfunction "GPIO_76_P8.39") (pintype "bidirectional"))
    )
    (net (code "105") (name "unconnected-(U$2A-GPIO_77-PadP8.40)") (class "Default")
      (node (ref "U$2") (pin "P8.40") (pinfunction "GPIO_77_P8.40") (pintype "bidirectional"))
    )
    (net (code "106") (name "unconnected-(U$2A-GPIO_78-PadP8.37)") (class "Default")
      (node (ref "U$2") (pin "P8.37") (pinfunction "GPIO_78_P8.37") (pintype "bidirectional"))
    )
    (net (code "107") (name "unconnected-(U$2A-GPIO_79-PadP8.38)") (class "Default")
      (node (ref "U$2") (pin "P8.38") (pinfunction "GPIO_79_P8.38") (pintype "bidirectional"))
    )
    (net (code "108") (name "unconnected-(U$2A-GPIO_80-PadP8.36)") (class "Default")
      (node (ref "U$2") (pin "P8.36") (pinfunction "GPIO_80_P8.36") (pintype "bidirectional"))
    )
    (net (code "109") (name "unconnected-(U$2A-GPIO_81-PadP8.34)") (class "Default")
      (node (ref "U$2") (pin "P8.34") (pinfunction "GPIO_81_P8.34") (pintype "bidirectional"))
    )
    (net (code "110") (name "unconnected-(U$2A-GPIO_86-PadP8.27)") (class "Default")
      (node (ref "U$2") (pin "P8.27") (pinfunction "GPIO_86_P8.27") (pintype "bidirectional"))
    )
    (net (code "111") (name "unconnected-(U$2A-GPIO_87-PadP8.29)") (class "Default")
      (node (ref "U$2") (pin "P8.29") (pinfunction "GPIO_87_P8.29") (pintype "bidirectional"))
    )
    (net (code "112") (name "unconnected-(U$2A-GPIO_88-PadP8.28)") (class "Default")
      (node (ref "U$2") (pin "P8.28") (pinfunction "GPIO_88_P8.28") (pintype "bidirectional"))
    )
    (net (code "113") (name "unconnected-(U$2A-GPIO_89-PadP8.30)") (class "Default")
      (node (ref "U$2") (pin "P8.30") (pinfunction "GPIO_89_P8.30") (pintype "bidirectional"))
    )
    (net (code "114") (name "unconnected-(U$2B-AIN0-PadP9.39)") (class "Default")
      (node (ref "U$2") (pin "P9.39") (pinfunction "AIN0_P9.39") (pintype "bidirectional"))
    )
    (net (code "115") (name "unconnected-(U$2B-AIN1-PadP9.40)") (class "Default")
      (node (ref "U$2") (pin "P9.40") (pinfunction "AIN1_P9.40") (pintype "bidirectional"))
    )
    (net (code "116") (name "unconnected-(U$2B-AIN2-PadP9.37)") (class "Default")
      (node (ref "U$2") (pin "P9.37") (pinfunction "AIN2_P9.37") (pintype "bidirectional"))
    )
    (net (code "117") (name "unconnected-(U$2B-AIN3-PadP9.38)") (class "Default")
      (node (ref "U$2") (pin "P9.38") (pinfunction "AIN3_P9.38") (pintype "bidirectional"))
    )
    (net (code "118") (name "unconnected-(U$2B-AIN4-PadP9.33)") (class "Default")
      (node (ref "U$2") (pin "P9.33") (pinfunction "AIN4_P9.33") (pintype "bidirectional"))
    )
    (net (code "119") (name "unconnected-(U$2B-AIN5-PadP9.36)") (class "Default")
      (node (ref "U$2") (pin "P9.36") (pinfunction "AIN5_P9.36") (pintype "bidirectional"))
    )
    (net (code "120") (name "unconnected-(U$2B-AIN6-PadP9.35)") (class "Default")
      (node (ref "U$2") (pin "P9.35") (pinfunction "AIN6_P9.35") (pintype "bidirectional"))
    )
    (net (code "121") (name "unconnected-(U$2B-GNDA_ADC-PadP9.34)") (class "Default")
      (node (ref "U$2") (pin "P9.34") (pinfunction "GNDA_ADC_P9.34") (pintype "bidirectional"))
    )
    (net (code "122") (name "unconnected-(U$2B-GPIO_14-PadP9.26)") (class "Default")
      (node (ref "U$2") (pin "P9.26") (pinfunction "GPIO_14_P9.26") (pintype "bidirectional"))
    )
    (net (code "123") (name "unconnected-(U$2B-GPIO_20-PadP9.41)") (class "Default")
      (node (ref "U$2") (pin "P9.41") (pinfunction "GPIO_20_P9.41") (pintype "bidirectional"))
    )
    (net (code "124") (name "unconnected-(U$2B-GPIO_40-PadP9.14)") (class "Default")
      (node (ref "U$2") (pin "P9.14") (pinfunction "GPIO_40_P9.14") (pintype "bidirectional"))
    )
    (net (code "125") (name "unconnected-(U$2B-GPIO_51-PadP9.16)") (class "Default")
      (node (ref "U$2") (pin "P9.16") (pinfunction "GPIO_51_P9.16") (pintype "bidirectional"))
    )
    (net (code "126") (name "unconnected-(U$2B-GPIO_60-PadP9.12)") (class "Default")
      (node (ref "U$2") (pin "P9.12") (pinfunction "GPIO_60_P9.12") (pintype "bidirectional"))
    )
    (net (code "127") (name "unconnected-(U$2B-GPIO_117-PadP9.25)") (class "Default")
      (node (ref "U$2") (pin "P9.25") (pinfunction "GPIO_117_P9.25") (pintype "bidirectional"))
    )
    (net (code "128") (name "unconnected-(U$2B-GPIO_125-PadP9.27)") (class "Default")
      (node (ref "U$2") (pin "P9.27") (pinfunction "GPIO_125_P9.27") (pintype "bidirectional"))
    )
    (net (code "129") (name "unconnected-(U$2B-PWR_BUT-PadP9.9)") (class "Default")
      (node (ref "U$2") (pin "P9.9") (pinfunction "PWR_BUT_P9.9") (pintype "bidirectional"))
    )
    (net (code "130") (name "unconnected-(U$2B-SYS_5V-PadP9.7)") (class "Default")
      (node (ref "U$2") (pin "P9.7") (pinfunction "SYS_5V_P9.7") (pintype "bidirectional"))
    )
    (net (code "131") (name "unconnected-(U$2B-SYS_5V-PadP9.8)") (class "Default")
      (node (ref "U$2") (pin "P9.8") (pinfunction "SYS_5V_P9.8") (pintype "bidirectional"))
    )
    (net (code "132") (name "unconnected-(U$2B-VDD_5V-PadP9.5)") (class "Default")
      (node (ref "U$2") (pin "P9.5") (pinfunction "VDD_5V_P9.5") (pintype "bidirectional"))
    )
    (net (code "133") (name "unconnected-(U$2B-VDD_5V-PadP9.6)") (class "Default")
      (node (ref "U$2") (pin "P9.6") (pinfunction "VDD_5V_P9.6") (pintype "bidirectional"))
    )
    (net (code "134") (name "unconnected-(U$2B-VDD_ADC-PadP9.32)") (class "Default")
      (node (ref "U$2") (pin "P9.32") (pinfunction "VDD_ADC_P9.32") (pintype "bidirectional"))
    )
    (net (code "135") (name "unconnected-(U$3-~{INT}-Pad17)") (class "Default")
      (node (ref "U$3") (pin "17") (pinfunction "~{INT}_17") (pintype "output"))
    )
    (net (code "136") (name "unconnected-(U$5-HOLD_~{THRU}-Pad5)") (class "Default")
      (node (ref "U$5") (pin "5") (pinfunction "HOLD_~{THRU}_5") (pintype "bidirectional"))
    )
    (net (code "137") (name "unconnected-(U$5-SHDN-Pad1)") (class "Default")
      (node (ref "U$5") (pin "1") (pinfunction "SHDN_1") (pintype "bidirectional"))
    )
    (net (code "138") (name "unconnected-(U$6-HOLD_~{THRU}-Pad5)") (class "Default")
      (node (ref "U$6") (pin "5") (pinfunction "HOLD_~{THRU}_5") (pintype "bidirectional"))
    )
    (net (code "139") (name "unconnected-(U$6-SHDN-Pad1)") (class "Default")
      (node (ref "U$6") (pin "1") (pinfunction "SHDN_1") (pintype "bidirectional"))
    )
    (net (code "140") (name "unconnected-(U$7-HOLD_~{THRU}-Pad5)") (class "Default")
      (node (ref "U$7") (pin "5") (pinfunction "HOLD_~{THRU}_5") (pintype "bidirectional"))
    )
    (net (code "141") (name "unconnected-(U$7-SHDN-Pad1)") (class "Default")
      (node (ref "U$7") (pin "1") (pinfunction "SHDN_1") (pintype "bidirectional"))
    )
    (net (code "142") (name "unconnected-(U$8-HOLD_~{THRU}-Pad5)") (class "Default")
      (node (ref "U$8") (pin "5") (pinfunction "HOLD_~{THRU}_5") (pintype "bidirectional"))
    )
    (net (code "143") (name "unconnected-(U$8-SHDN-Pad1)") (class "Default")
      (node (ref "U$8") (pin "1") (pinfunction "SHDN_1") (pintype "bidirectional"))
    )
    (net (code "144") (name "unconnected-(U3-DEN_A{slash}G-Pad13)") (class "Default")
      (node (ref "U3") (pin "13") (pinfunction "DEN_A/G_13") (pintype "bidirectional"))
    )
    (net (code "145") (name "unconnected-(U3-DRDY_M-Pad9)") (class "Default")
      (node (ref "U3") (pin "9") (pinfunction "DRDY_M_9") (pintype "bidirectional"))
    )
    (net (code "146") (name "unconnected-(U3-INT1_A{slash}G-Pad11)") (class "Default")
      (node (ref "U3") (pin "11") (pinfunction "INT1_A/G_11") (pintype "bidirectional"))
    )
    (net (code "147") (name "unconnected-(U3-INT2_A{slash}G-Pad12)") (class "Default")
      (node (ref "U3") (pin "12") (pinfunction "INT2_A/G_12") (pintype "bidirectional"))
    )
    (net (code "148") (name "unconnected-(U3-INT_M-Pad10)") (class "Default")
      (node (ref "U3") (pin "10") (pinfunction "INT_M_10") (pintype "bidirectional"))
    )
  )
)
